# ESP32_ADC_HUB.net
KiCad netlist of a schematic drawn in EAGLE
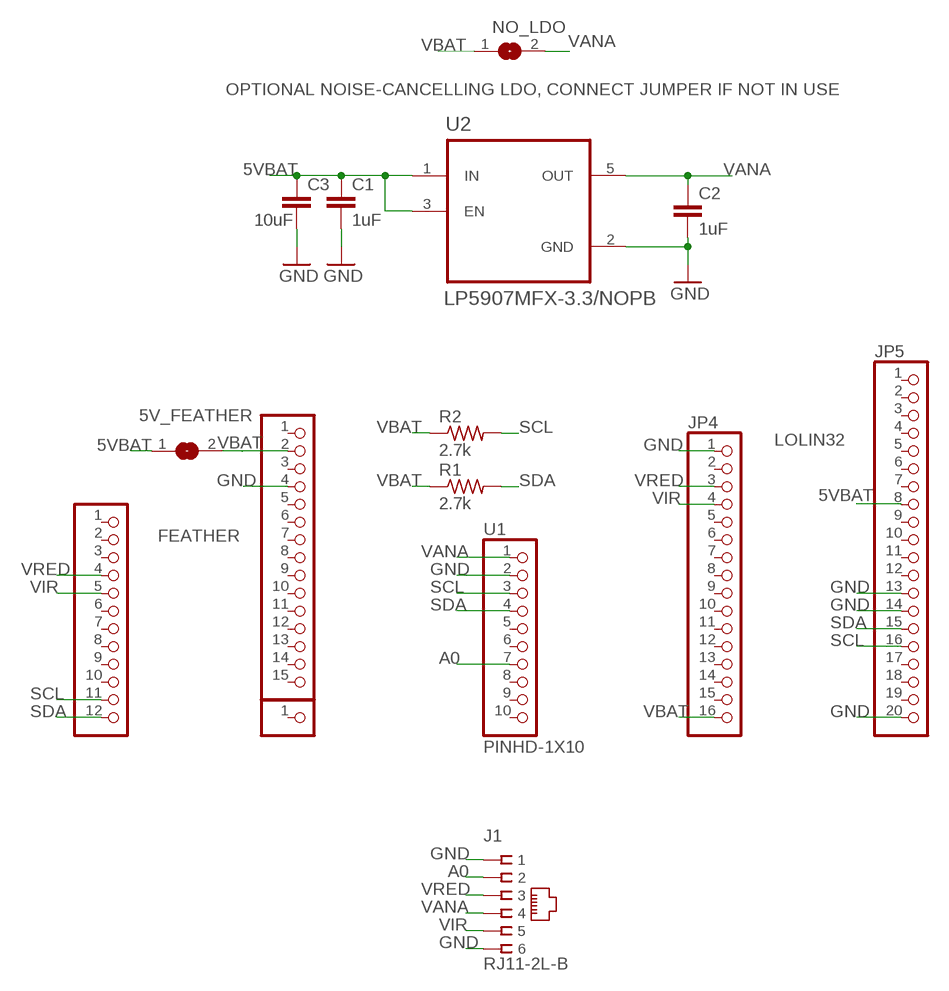
[diagram p0: schematic, sheet 1]

(export (version "E")
  (design (tool "Eeschema 10.0.6"))
  (components
    (comp (ref "5V_FEATHER")
      (value "SJ")
      (footprint "eagle-import:SJ")
      (libsource (lib "eagle-import") (part "SJ"))
    )
    (comp (ref "C1")
      (value "1uF")
      (footprint "eagle-import:C050-024X044")
      (libsource (lib "eagle-import") (part "C-EU050-024X044"))
    )
    (comp (ref "C2")
      (value "1uF")
      (footprint "eagle-import:C050-024X044")
      (libsource (lib "eagle-import") (part "C-EU050-024X044"))
    )
    (comp (ref "C3")
      (value "10uF")
      (footprint "eagle-import:C050-024X044")
      (libsource (lib "eagle-import") (part "C-EU050-024X044"))
    )
    (comp (ref "J1")
      (value "RJ11-2L-B")
      (footprint "eagle-import:RJ11-NO_SHIELD")
      (fields (field (name "MF") "TYCO ELECTRONICS"))
      (libsource (lib "eagle-import") (part "RJ11-2L-B"))
    )
    (comp (ref "JP1")
      (value "PINHD-1X12-CB")
      (footprint "eagle-import:1X12-CB")
      (libsource (lib "eagle-import") (part "PINHD-1X12-CB"))
    )
    (comp (ref "JP2")
      (value "PINHD-1X15-CB")
      (footprint "eagle-import:1X15-CB")
      (libsource (lib "eagle-import") (part "PINHD-1X15-CB"))
    )
    (comp (ref "JP3")
      (value "PINHD-1X1CB")
      (footprint "eagle-import:1X01-CLEANBIG")
      (libsource (lib "eagle-import") (part "PINHD-1X1CB"))
    )
    (comp (ref "JP4")
      (value "PINHD-1X16")
      (footprint "eagle-import:1X16")
      (libsource (lib "eagle-import") (part "PINHD-1X16"))
    )
    (comp (ref "JP5")
      (value "PINHD-1X20")
      (footprint "eagle-import:1X20")
      (libsource (lib "eagle-import") (part "PINHD-1X20"))
    )
    (comp (ref "NO_LDO")
      (value "SJ")
      (footprint "eagle-import:SJ")
      (libsource (lib "eagle-import") (part "SJ"))
    )
    (comp (ref "R1")
      (value "2.7k")
      (footprint "eagle-import:0204_7")
      (libsource (lib "eagle-import") (part "R-US_0204/7"))
    )
    (comp (ref "R2")
      (value "2.7k")
      (footprint "eagle-import:0204_7")
      (libsource (lib "eagle-import") (part "R-US_0204/7"))
    )
    (comp (ref "U1")
      (value "PINHD-1X10")
      (footprint "eagle-import:1X10-BIG")
      (libsource (lib "eagle-import") (part "PINHD-1X10"))
    )
    (comp (ref "U2")
      (value "LP5907MFX-3.3/NOPB")
      (footprint "eagle-import:SOT95P280X145-5N")
      (fields (field (name "MF") "Texas Instruments"))
      (libsource (lib "eagle-import") (part "LP5907MFX-3.3/NOPB"))
    )
  )
  (nets
    (net (code "1") (name "/5VBAT") (class "Default")
      (node (ref "5V_FEATHER") (pin "1") (pinfunction "1_1") (pintype "passive"))
      (node (ref "C1") (pin "1") (pinfunction "1_1") (pintype "passive"))
      (node (ref "C3") (pin "1") (pinfunction "1_1") (pintype "passive"))
      (node (ref "JP5") (pin "8") (pinfunction "8_8") (pintype "passive"))
      (node (ref "U2") (pin "1") (pinfunction "IN_1") (pintype "input"))
      (node (ref "U2") (pin "3") (pinfunction "EN_3") (pintype "input"))
    )
    (net (code "2") (name "/A0") (class "Default")
      (node (ref "J1") (pin "2") (pinfunction "2_2") (pintype "passive"))
      (node (ref "U1") (pin "7") (pinfunction "7_7") (pintype "passive"))
    )
    (net (code "3") (name "/SCL") (class "Default")
      (node (ref "JP1") (pin "11") (pinfunction "11_11") (pintype "passive"))
      (node (ref "JP5") (pin "16") (pinfunction "16_16") (pintype "passive"))
      (node (ref "R2") (pin "2") (pinfunction "2_2") (pintype "passive"))
      (node (ref "U1") (pin "3") (pinfunction "3_3") (pintype "passive"))
    )
    (net (code "4") (name "/SDA") (class "Default")
      (node (ref "JP1") (pin "12") (pinfunction "12_12") (pintype "passive"))
      (node (ref "JP5") (pin "15") (pinfunction "15_15") (pintype "passive"))
      (node (ref "R1") (pin "2") (pinfunction "2_2") (pintype "passive"))
      (node (ref "U1") (pin "4") (pinfunction "4_4") (pintype "passive"))
    )
    (net (code "5") (name "/VANA") (class "Default")
      (node (ref "C2") (pin "1") (pinfunction "1_1") (pintype "passive"))
      (node (ref "J1") (pin "4") (pinfunction "4_4") (pintype "passive"))
      (node (ref "NO_LDO") (pin "2") (pinfunction "2_2") (pintype "passive"))
      (node (ref "U1") (pin "1") (pinfunction "1_1") (pintype "passive"))
      (node (ref "U2") (pin "5") (pinfunction "OUT_5") (pintype "output"))
    )
    (net (code "6") (name "/VBAT") (class "Default")
      (node (ref "5V_FEATHER") (pin "2") (pinfunction "2_2") (pintype "passive"))
      (node (ref "JP2") (pin "2") (pinfunction "2_2") (pintype "passive"))
      (node (ref "JP4") (pin "16") (pinfunction "16_16") (pintype "passive"))
      (node (ref "NO_LDO") (pin "1") (pinfunction "1_1") (pintype "passive"))
      (node (ref "R1") (pin "1") (pinfunction "1_1") (pintype "passive"))
      (node (ref "R2") (pin "1") (pinfunction "1_1") (pintype "passive"))
    )
    (net (code "7") (name "/VIR") (class "Default")
      (node (ref "J1") (pin "5") (pinfunction "5_5") (pintype "passive"))
      (node (ref "JP1") (pin "5") (pinfunction "5_5") (pintype "passive"))
      (node (ref "JP4") (pin "4") (pinfunction "4_4") (pintype "passive"))
    )
    (net (code "8") (name "/VRED") (class "Default")
      (node (ref "J1") (pin "3") (pinfunction "3_3") (pintype "passive"))
      (node (ref "JP1") (pin "4") (pinfunction "4_4") (pintype "passive"))
      (node (ref "JP4") (pin "3") (pinfunction "3_3") (pintype "passive"))
    )
    (net (code "9") (name "GND") (class "Default")
      (node (ref "C1") (pin "2") (pinfunction "2_2") (pintype "passive"))
      (node (ref "C2") (pin "2") (pinfunction "2_2") (pintype "passive"))
      (node (ref "C3") (pin "2") (pinfunction "2_2") (pintype "passive"))
      (node (ref "J1") (pin "1") (pinfunction "1_1") (pintype "passive"))
      (node (ref "J1") (pin "6") (pinfunction "6_6") (pintype "passive"))
      (node (ref "JP2") (pin "4") (pinfunction "4_4") (pintype "passive"))
      (node (ref "JP4") (pin "1") (pinfunction "1_1") (pintype "passive"))
      (node (ref "JP5") (pin "13") (pinfunction "13_13") (pintype "passive"))
      (node (ref "JP5") (pin "14") (pinfunction "14_14") (pintype "passive"))
      (node (ref "JP5") (pin "20") (pinfunction "20_20") (pintype "passive"))
      (node (ref "U1") (pin "2") (pinfunction "2_2") (pintype "passive"))
      (node (ref "U2") (pin "2") (pinfunction "GND_2") (pintype "power_in"))
    )
    (net (code "10") (name "unconnected-(JP1-Pad1)") (class "Default")
      (node (ref "JP1") (pin "1") (pinfunction "1_1") (pintype "passive"))
    )
    (net (code "11") (name "unconnected-(JP1-Pad2)") (class "Default")
      (node (ref "JP1") (pin "2") (pinfunction "2_2") (pintype "passive"))
    )
    (net (code "12") (name "unconnected-(JP1-Pad3)") (class "Default")
      (node (ref "JP1") (pin "3") (pinfunction "3_3") (pintype "passive"))
    )
    (net (code "13") (name "unconnected-(JP1-Pad6)") (class "Default")
      (node (ref "JP1") (pin "6") (pinfunction "6_6") (pintype "passive"))
    )
    (net (code "14") (name "unconnected-(JP1-Pad7)") (class "Default")
      (node (ref "JP1") (pin "7") (pinfunction "7_7") (pintype "passive"))
    )
    (net (code "15") (name "unconnected-(JP1-Pad8)") (class "Default")
      (node (ref "JP1") (pin "8") (pinfunction "8_8") (pintype "passive"))
    )
    (net (code "16") (name "unconnected-(JP1-Pad9)") (class "Default")
      (node (ref "JP1") (pin "9") (pinfunction "9_9") (pintype "passive"))
    )
    (net (code "17") (name "unconnected-(JP1-Pad10)") (class "Default")
      (node (ref "JP1") (pin "10") (pinfunction "10_10") (pintype "passive"))
    )
    (net (code "18") (name "unconnected-(JP2-Pad1)") (class "Default")
      (node (ref "JP2") (pin "1") (pinfunction "1_1") (pintype "passive"))
    )
    (net (code "19") (name "unconnected-(JP2-Pad3)") (class "Default")
      (node (ref "JP2") (pin "3") (pinfunction "3_3") (pintype "passive"))
    )
    (net (code "20") (name "unconnected-(JP2-Pad5)") (class "Default")
      (node (ref "JP2") (pin "5") (pinfunction "5_5") (pintype "passive"))
    )
    (net (code "21") (name "unconnected-(JP2-Pad6)") (class "Default")
      (node (ref "JP2") (pin "6") (pinfunction "6_6") (pintype "passive"))
    )
    (net (code "22") (name "unconnected-(JP2-Pad7)") (class "Default")
      (node (ref "JP2") (pin "7") (pinfunction "7_7") (pintype "passive"))
    )
    (net (code "23") (name "unconnected-(JP2-Pad8)") (class "Default")
      (node (ref "JP2") (pin "8") (pinfunction "8_8") (pintype "passive"))
    )
    (net (code "24") (name "unconnected-(JP2-Pad9)") (class "Default")
      (node (ref "JP2") (pin "9") (pinfunction "9_9") (pintype "passive"))
    )
    (net (code "25") (name "unconnected-(JP2-Pad10)") (class "Default")
      (node (ref "JP2") (pin "10") (pinfunction "10_10") (pintype "passive"))
    )
    (net (code "26") (name "unconnected-(JP2-Pad11)") (class "Default")
      (node (ref "JP2") (pin "11") (pinfunction "11_11") (pintype "passive"))
    )
    (net (code "27") (name "unconnected-(JP2-Pad12)") (class "Default")
      (node (ref "JP2") (pin "12") (pinfunction "12_12") (pintype "passive"))
    )
    (net (code "28") (name "unconnected-(JP2-Pad13)") (class "Default")
      (node (ref "JP2") (pin "13") (pinfunction "13_13") (pintype "passive"))
    )
    (net (code "29") (name "unconnected-(JP2-Pad14)") (class "Default")
      (node (ref "JP2") (pin "14") (pinfunction "14_14") (pintype "passive"))
    )
    (net (code "30") (name "unconnected-(JP2-Pad15)") (class "Default")
      (node (ref "JP2") (pin "15") (pinfunction "15_15") (pintype "passive"))
    )
    (net (code "31") (name "unconnected-(JP3-Pad1)") (class "Default")
      (node (ref "JP3") (pin "1") (pinfunction "1_1") (pintype "passive"))
    )
    (net (code "32") (name "unconnected-(JP4-Pad2)") (class "Default")
      (node (ref "JP4") (pin "2") (pinfunction "2_2") (pintype "passive"))
    )
    (net (code "33") (name "unconnected-(JP4-Pad5)") (class "Default")
      (node (ref "JP4") (pin "5") (pinfunction "5_5") (pintype "passive"))
    )
    (net (code "34") (name "unconnected-(JP4-Pad6)") (class "Default")
      (node (ref "JP4") (pin "6") (pinfunction "6_6") (pintype "passive"))
    )
    (net (code "35") (name "unconnected-(JP4-Pad7)") (class "Default")
      (node (ref "JP4") (pin "7") (pinfunction "7_7") (pintype "passive"))
    )
    (net (code "36") (name "unconnected-(JP4-Pad8)") (class "Default")
      (node (ref "JP4") (pin "8") (pinfunction "8_8") (pintype "passive"))
    )
    (net (code "37") (name "unconnected-(JP4-Pad9)") (class "Default")
      (node (ref "JP4") (pin "9") (pinfunction "9_9") (pintype "passive"))
    )
    (net (code "38") (name "unconnected-(JP4-Pad10)") (class "Default")
      (node (ref "JP4") (pin "10") (pinfunction "10_10") (pintype "passive"))
    )
    (net (code "39") (name "unconnected-(JP4-Pad11)") (class "Default")
      (node (ref "JP4") (pin "11") (pinfunction "11_11") (pintype "passive"))
    )
    (net (code "40") (name "unconnected-(JP4-Pad12)") (class "Default")
      (node (ref "JP4") (pin "12") (pinfunction "12_12") (pintype "passive"))
    )
    (net (code "41") (name "unconnected-(JP4-Pad13)") (class "Default")
      (node (ref "JP4") (pin "13") (pinfunction "13_13") (pintype "passive"))
    )
    (net (code "42") (name "unconnected-(JP4-Pad14)") (class "Default")
      (node (ref "JP4") (pin "14") (pinfunction "14_14") (pintype "passive"))
    )
    (net (code "43") (name "unconnected-(JP4-Pad15)") (class "Default")
      (node (ref "JP4") (pin "15") (pinfunction "15_15") (pintype "passive"))
    )
    (net (code "44") (name "unconnected-(JP5-Pad1)") (class "Default")
      (node (ref "JP5") (pin "1") (pinfunction "1_1") (pintype "passive"))
    )
    (net (code "45") (name "unconnected-(JP5-Pad2)") (class "Default")
      (node (ref "JP5") (pin "2") (pinfunction "2_2") (pintype "passive"))
    )
    (net (code "46") (name "unconnected-(JP5-Pad3)") (class "Default")
      (node (ref "JP5") (pin "3") (pinfunction "3_3") (pintype "passive"))
    )
    (net (code "47") (name "unconnected-(JP5-Pad4)") (class "Default")
      (node (ref "JP5") (pin "4") (pinfunction "4_4") (pintype "passive"))
    )
    (net (code "48") (name "unconnected-(JP5-Pad5)") (class "Default")
      (node (ref "JP5") (pin "5") (pinfunction "5_5") (pintype "passive"))
    )
    (net (code "49") (name "unconnected-(JP5-Pad6)") (class "Default")
      (node (ref "JP5") (pin "6") (pinfunction "6_6") (pintype "passive"))
    )
    (net (code "50") (name "unconnected-(JP5-Pad7)") (class "Default")
      (node (ref "JP5") (pin "7") (pinfunction "7_7") (pintype "passive"))
    )
    (net (code "51") (name "unconnected-(JP5-Pad9)") (class "Default")
      (node (ref "JP5") (pin "9") (pinfunction "9_9") (pintype "passive"))
    )
    (net (code "52") (name "unconnected-(JP5-Pad10)") (class "Default")
      (node (ref "JP5") (pin "10") (pinfunction "10_10") (pintype "passive"))
    )
    (net (code "53") (name "unconnected-(JP5-Pad11)") (class "Default")
      (node (ref "JP5") (pin "11") (pinfunction "11_11") (pintype "passive"))
    )
    (net (code "54") (name "unconnected-(JP5-Pad12)") (class "Default")
      (node (ref "JP5") (pin "12") (pinfunction "12_12") (pintype "passive"))
    )
    (net (code "55") (name "unconnected-(JP5-Pad17)") (class "Default")
      (node (ref "JP5") (pin "17") (pinfunction "17_17") (pintype "passive"))
    )
    (net (code "56") (name "unconnected-(JP5-Pad18)") (class "Default")
      (node (ref "JP5") (pin "18") (pinfunction "18_18") (pintype "passive"))
    )
    (net (code "57") (name "unconnected-(JP5-Pad19)") (class "Default")
      (node (ref "JP5") (pin "19") (pinfunction "19_19") (pintype "passive"))
    )
    (net (code "58") (name "unconnected-(U1-Pad5)") (class "Default")
      (node (ref "U1") (pin "5") (pinfunction "5_5") (pintype "passive"))
    )
    (net (code "59") (name "unconnected-(U1-Pad6)") (class "Default")
      (node (ref "U1") (pin "6") (pinfunction "6_6") (pintype "passive"))
    )
    (net (code "60") (name "unconnected-(U1-Pad8)") (class "Default")
      (node (ref "U1") (pin "8") (pinfunction "8_8") (pintype "passive"))
    )
    (net (code "61") (name "unconnected-(U1-Pad9)") (class "Default")
      (node (ref "U1") (pin "9") (pinfunction "9_9") (pintype "passive"))
    )
    (net (code "62") (name "unconnected-(U1-Pad10)") (class "Default")
      (node (ref "U1") (pin "10") (pinfunction "10_10") (pintype "passive"))
    )
  )
)
